# esp8266_db.net
KiCad netlist of a schematic drawn in EAGLE
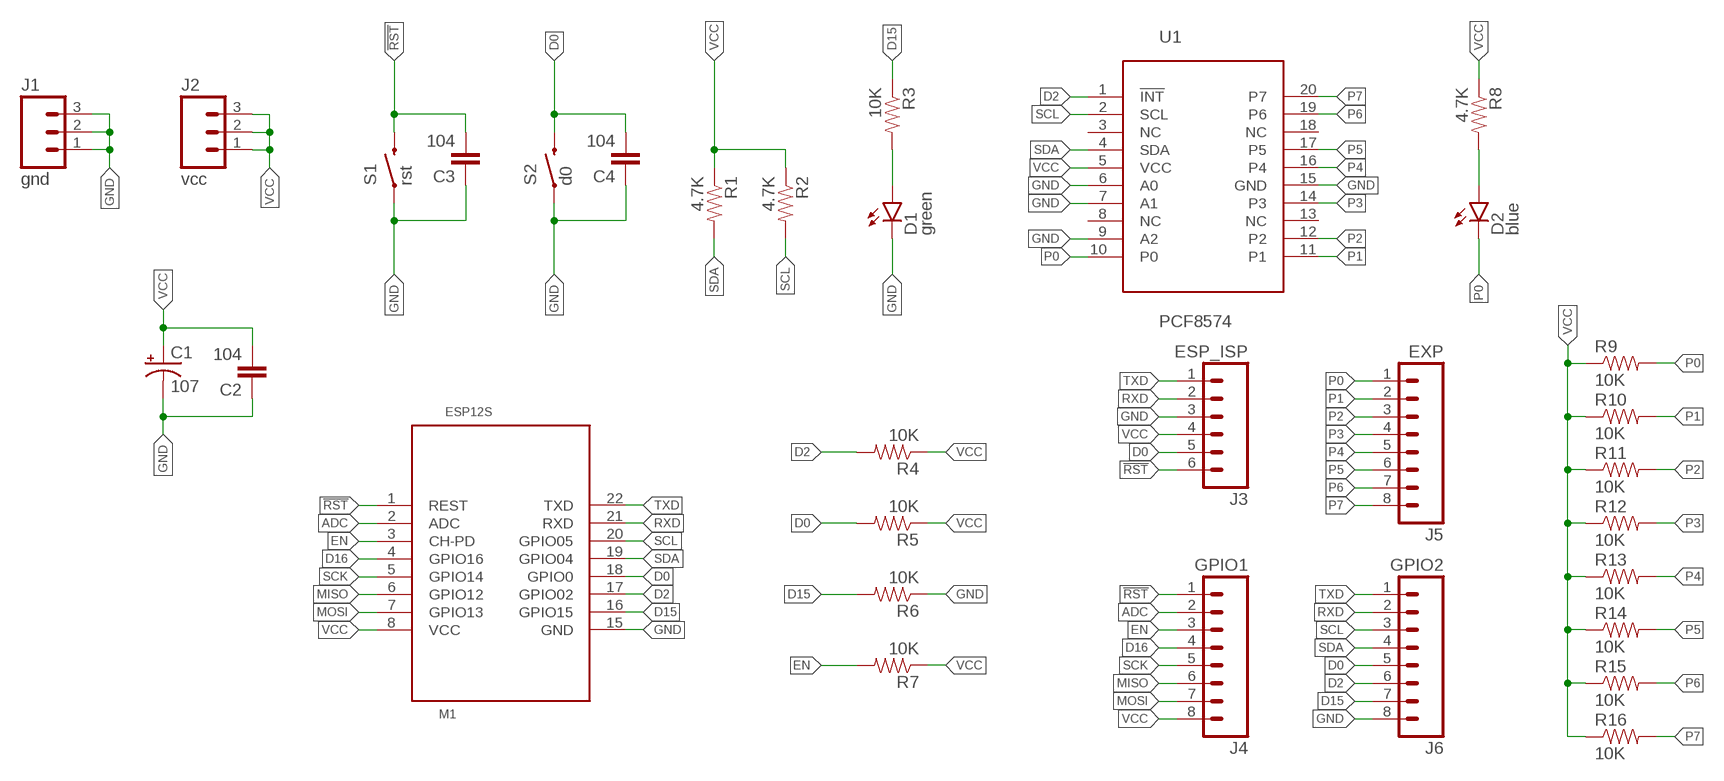
[diagram p0: schematic, sheet 1]

(export (version "E")
  (design (tool "Eeschema 10.0.6"))
  (components
    (comp (ref "C1")
      (value "107")
      (footprint "eagle-import:EIA3528")
      (libsource (lib "eagle-import") (part "CAP_POL3528"))
    )
    (comp (ref "C2")
      (value "104")
      (footprint "eagle-import:0603-CAP")
      (libsource (lib "eagle-import") (part "CAP0603-CAP"))
    )
    (comp (ref "C3")
      (value "104")
      (footprint "eagle-import:0603-CAP")
      (libsource (lib "eagle-import") (part "CAP0603-CAP"))
    )
    (comp (ref "C4")
      (value "104")
      (footprint "eagle-import:0603-CAP")
      (libsource (lib "eagle-import") (part "CAP0603-CAP"))
    )
    (comp (ref "D1")
      (value "green")
      (footprint "eagle-import:LED-0603-EASY")
      (libsource (lib "eagle-import") (part "LED-EASY"))
    )
    (comp (ref "D2")
      (value "blue")
      (footprint "eagle-import:LED-0603-EASY")
      (libsource (lib "eagle-import") (part "LED-EASY"))
    )
    (comp (ref "J1")
      (value "gnd")
      (footprint "eagle-import:1X03_NO_SILK")
      (libsource (lib "eagle-import") (part "M031X03_NO_SILK"))
    )
    (comp (ref "J2")
      (value "vcc")
      (footprint "eagle-import:1X03_NO_SILK")
      (libsource (lib "eagle-import") (part "M031X03_NO_SILK"))
    )
    (comp (ref "J3")
      (value "ESP_ISP")
      (footprint "eagle-import:1X06_NO_SILK")
      (libsource (lib "eagle-import") (part "M06NO_SILK_FEMALE_PTH"))
    )
    (comp (ref "J4")
      (value "GPIO1")
      (footprint "eagle-import:1X08_NO_SILK")
      (libsource (lib "eagle-import") (part "M08NO_SILK_FEMALE_PTH"))
    )
    (comp (ref "J5")
      (value "EXP")
      (footprint "eagle-import:1X08_NO_SILK")
      (libsource (lib "eagle-import") (part "M08NO_SILK_FEMALE_PTH"))
    )
    (comp (ref "J6")
      (value "GPIO2")
      (footprint "eagle-import:1X08_NO_SILK")
      (libsource (lib "eagle-import") (part "M08NO_SILK_FEMALE_PTH"))
    )
    (comp (ref "M1")
      (value "ESP12S")
      (footprint "eagle-import:LGA22-2.0-24X16MM-SIMPLE")
      (libsource (lib "eagle-import") (part "MODULE-WIFI-ESP8266-12E-SIMPLE"))
    )
    (comp (ref "R1")
      (value "4.7K")
      (footprint "eagle-import:0603-RES")
      (libsource (lib "eagle-import") (part "RESISTOR0603"))
    )
    (comp (ref "R2")
      (value "4.7K")
      (footprint "eagle-import:0603-RES")
      (libsource (lib "eagle-import") (part "RESISTOR0603"))
    )
    (comp (ref "R3")
      (value "10K")
      (footprint "eagle-import:0603-RES")
      (libsource (lib "eagle-import") (part "RESISTOR0603"))
    )
    (comp (ref "R4")
      (value "10K")
      (footprint "eagle-import:0603-RES")
      (libsource (lib "eagle-import") (part "RESISTOR0603"))
    )
    (comp (ref "R5")
      (value "10K")
      (footprint "eagle-import:0603-RES")
      (libsource (lib "eagle-import") (part "RESISTOR0603"))
    )
    (comp (ref "R6")
      (value "10K")
      (footprint "eagle-import:0603-RES")
      (libsource (lib "eagle-import") (part "RESISTOR0603"))
    )
    (comp (ref "R7")
      (value "10K")
      (footprint "eagle-import:0603-RES")
      (libsource (lib "eagle-import") (part "RESISTOR0603"))
    )
    (comp (ref "R8")
      (value "4.7K")
      (footprint "eagle-import:0603-RES")
      (libsource (lib "eagle-import") (part "RESISTOR0603"))
    )
    (comp (ref "R9")
      (value "10K")
      (footprint "eagle-import:0603-RES")
      (libsource (lib "eagle-import") (part "RESISTOR0603"))
    )
    (comp (ref "R10")
      (value "10K")
      (footprint "eagle-import:0603-RES")
      (libsource (lib "eagle-import") (part "RESISTOR0603"))
    )
    (comp (ref "R11")
      (value "10K")
      (footprint "eagle-import:0603-RES")
      (libsource (lib "eagle-import") (part "RESISTOR0603"))
    )
    (comp (ref "R12")
      (value "10K")
      (footprint "eagle-import:0603-RES")
      (libsource (lib "eagle-import") (part "RESISTOR0603"))
    )
    (comp (ref "R13")
      (value "10K")
      (footprint "eagle-import:0603-RES")
      (libsource (lib "eagle-import") (part "RESISTOR0603"))
    )
    (comp (ref "R14")
      (value "10K")
      (footprint "eagle-import:0603-RES")
      (libsource (lib "eagle-import") (part "RESISTOR0603"))
    )
    (comp (ref "R15")
      (value "10K")
      (footprint "eagle-import:0603-RES")
      (libsource (lib "eagle-import") (part "RESISTOR0603"))
    )
    (comp (ref "R16")
      (value "10K")
      (footprint "eagle-import:0603-RES")
      (libsource (lib "eagle-import") (part "RESISTOR0603"))
    )
    (comp (ref "S1")
      (value "rst")
      (footprint "eagle-import:TACTILE-PTH")
      (libsource (lib "eagle-import") (part "SWITCH-MOMENTARY-2PTH"))
    )
    (comp (ref "S2")
      (value "d0")
      (footprint "eagle-import:TACTILE-PTH")
      (libsource (lib "eagle-import") (part "SWITCH-MOMENTARY-2PTH"))
    )
    (comp (ref "U1")
      (value "PCF8574")
      (footprint "eagle-import:TSSOP20")
      (libsource (lib "eagle-import") (part "PCF8574"))
    )
  )
  (nets
    (net (code "1") (name "/~{RST}") (class "Default")
      (node (ref "C3") (pin "2") (pinfunction "2_2") (pintype "passive"))
      (node (ref "J3") (pin "6") (pinfunction "6_6") (pintype "passive"))
      (node (ref "J4") (pin "1") (pinfunction "1_1") (pintype "passive"))
      (node (ref "M1") (pin "1") (pinfunction "REST_1") (pintype "bidirectional"))
      (node (ref "S1") (pin "3") (pinfunction "2_3") (pintype "passive"))
    )
    (net (code "2") (name "ADC") (class "Default")
      (node (ref "J4") (pin "2") (pinfunction "2_2") (pintype "passive"))
      (node (ref "M1") (pin "2") (pinfunction "ADC_2") (pintype "bidirectional"))
    )
    (net (code "3") (name "D0") (class "Default")
      (node (ref "C4") (pin "2") (pinfunction "2_2") (pintype "passive"))
      (node (ref "J3") (pin "5") (pinfunction "5_5") (pintype "passive"))
      (node (ref "J6") (pin "5") (pinfunction "5_5") (pintype "passive"))
      (node (ref "M1") (pin "18") (pinfunction "GPIO0_18") (pintype "bidirectional"))
      (node (ref "R5") (pin "2") (pinfunction "2_2") (pintype "passive"))
      (node (ref "S2") (pin "3") (pinfunction "2_3") (pintype "passive"))
    )
    (net (code "4") (name "D2") (class "Default")
      (node (ref "J6") (pin "6") (pinfunction "6_6") (pintype "passive"))
      (node (ref "M1") (pin "17") (pinfunction "GPIO02_17") (pintype "bidirectional"))
      (node (ref "R4") (pin "2") (pinfunction "2_2") (pintype "passive"))
      (node (ref "U1") (pin "1") (pinfunction "~{INT}_1") (pintype "bidirectional"))
    )
    (net (code "5") (name "D15") (class "Default")
      (node (ref "J6") (pin "7") (pinfunction "7_7") (pintype "passive"))
      (node (ref "M1") (pin "16") (pinfunction "GPIO15_16") (pintype "bidirectional"))
      (node (ref "R3") (pin "1") (pinfunction "1_1") (pintype "passive"))
      (node (ref "R6") (pin "2") (pinfunction "2_2") (pintype "passive"))
    )
    (net (code "6") (name "D16") (class "Default")
      (node (ref "J4") (pin "4") (pinfunction "4_4") (pintype "passive"))
      (node (ref "M1") (pin "4") (pinfunction "GPIO16_4") (pintype "bidirectional"))
    )
    (net (code "7") (name "EN") (class "Default")
      (node (ref "J4") (pin "3") (pinfunction "3_3") (pintype "passive"))
      (node (ref "M1") (pin "3") (pinfunction "CH-PD_3") (pintype "bidirectional"))
      (node (ref "R7") (pin "2") (pinfunction "2_2") (pintype "passive"))
    )
    (net (code "8") (name "GND") (class "Default")
      (node (ref "C1") (pin "C") (pinfunction "-_C") (pintype "passive"))
      (node (ref "C2") (pin "1") (pinfunction "1_1") (pintype "passive"))
      (node (ref "C3") (pin "1") (pinfunction "1_1") (pintype "passive"))
      (node (ref "C4") (pin "1") (pinfunction "1_1") (pintype "passive"))
      (node (ref "D1") (pin "-") (pinfunction "C_-") (pintype "passive"))
      (node (ref "J1") (pin "1") (pinfunction "1_1") (pintype "passive"))
      (node (ref "J1") (pin "2") (pinfunction "2_2") (pintype "passive"))
      (node (ref "J1") (pin "3") (pinfunction "3_3") (pintype "passive"))
      (node (ref "J3") (pin "3") (pinfunction "3_3") (pintype "passive"))
      (node (ref "J6") (pin "8") (pinfunction "8_8") (pintype "passive"))
      (node (ref "M1") (pin "15") (pinfunction "GND_15") (pintype "bidirectional"))
      (node (ref "R6") (pin "1") (pinfunction "1_1") (pintype "passive"))
      (node (ref "S1") (pin "1") (pinfunction "1_1") (pintype "passive"))
      (node (ref "S2") (pin "1") (pinfunction "1_1") (pintype "passive"))
      (node (ref "U1") (pin "15") (pinfunction "GND_15") (pintype "bidirectional"))
      (node (ref "U1") (pin "6") (pinfunction "A0_6") (pintype "bidirectional"))
      (node (ref "U1") (pin "7") (pinfunction "A1_7") (pintype "bidirectional"))
      (node (ref "U1") (pin "9") (pinfunction "A2_9") (pintype "bidirectional"))
    )
    (net (code "9") (name "MISO") (class "Default")
      (node (ref "J4") (pin "6") (pinfunction "6_6") (pintype "passive"))
      (node (ref "M1") (pin "6") (pinfunction "GPIO12_6") (pintype "bidirectional"))
    )
    (net (code "10") (name "MOSI") (class "Default")
      (node (ref "J4") (pin "7") (pinfunction "7_7") (pintype "passive"))
      (node (ref "M1") (pin "7") (pinfunction "GPIO13_7") (pintype "bidirectional"))
    )
    (net (code "11") (name "Net-(D1-A)") (class "Default")
      (node (ref "D1") (pin "+") (pinfunction "A_+") (pintype "passive"))
      (node (ref "R3") (pin "2") (pinfunction "2_2") (pintype "passive"))
    )
    (net (code "12") (name "Net-(D2-A)") (class "Default")
      (node (ref "D2") (pin "+") (pinfunction "A_+") (pintype "passive"))
      (node (ref "R8") (pin "2") (pinfunction "2_2") (pintype "passive"))
    )
    (net (code "13") (name "P0") (class "Default")
      (node (ref "D2") (pin "-") (pinfunction "C_-") (pintype "passive"))
      (node (ref "J5") (pin "1") (pinfunction "1_1") (pintype "passive"))
      (node (ref "R9") (pin "2") (pinfunction "2_2") (pintype "passive"))
      (node (ref "U1") (pin "10") (pinfunction "P0_10") (pintype "bidirectional"))
    )
    (net (code "14") (name "P1") (class "Default")
      (node (ref "J5") (pin "2") (pinfunction "2_2") (pintype "passive"))
      (node (ref "R10") (pin "2") (pinfunction "2_2") (pintype "passive"))
      (node (ref "U1") (pin "11") (pinfunction "P1_11") (pintype "bidirectional"))
    )
    (net (code "15") (name "P2") (class "Default")
      (node (ref "J5") (pin "3") (pinfunction "3_3") (pintype "passive"))
      (node (ref "R11") (pin "2") (pinfunction "2_2") (pintype "passive"))
      (node (ref "U1") (pin "12") (pinfunction "P2_12") (pintype "bidirectional"))
    )
    (net (code "16") (name "P3") (class "Default")
      (node (ref "J5") (pin "4") (pinfunction "4_4") (pintype "passive"))
      (node (ref "R12") (pin "2") (pinfunction "2_2") (pintype "passive"))
      (node (ref "U1") (pin "14") (pinfunction "P3_14") (pintype "bidirectional"))
    )
    (net (code "17") (name "P4") (class "Default")
      (node (ref "J5") (pin "5") (pinfunction "5_5") (pintype "passive"))
      (node (ref "R13") (pin "2") (pinfunction "2_2") (pintype "passive"))
      (node (ref "U1") (pin "16") (pinfunction "P4_16") (pintype "bidirectional"))
    )
    (net (code "18") (name "P5") (class "Default")
      (node (ref "J5") (pin "6") (pinfunction "6_6") (pintype "passive"))
      (node (ref "R14") (pin "2") (pinfunction "2_2") (pintype "passive"))
      (node (ref "U1") (pin "17") (pinfunction "P5_17") (pintype "bidirectional"))
    )
    (net (code "19") (name "P6") (class "Default")
      (node (ref "J5") (pin "7") (pinfunction "7_7") (pintype "passive"))
      (node (ref "R15") (pin "2") (pinfunction "2_2") (pintype "passive"))
      (node (ref "U1") (pin "19") (pinfunction "P6_19") (pintype "bidirectional"))
    )
    (net (code "20") (name "P7") (class "Default")
      (node (ref "J5") (pin "8") (pinfunction "8_8") (pintype "passive"))
      (node (ref "R16") (pin "2") (pinfunction "2_2") (pintype "passive"))
      (node (ref "U1") (pin "20") (pinfunction "P7_20") (pintype "bidirectional"))
    )
    (net (code "21") (name "RXD") (class "Default")
      (node (ref "J3") (pin "2") (pinfunction "2_2") (pintype "passive"))
      (node (ref "J6") (pin "2") (pinfunction "2_2") (pintype "passive"))
      (node (ref "M1") (pin "21") (pinfunction "RXD_21") (pintype "bidirectional"))
    )
    (net (code "22") (name "SCK") (class "Default")
      (node (ref "J4") (pin "5") (pinfunction "5_5") (pintype "passive"))
      (node (ref "M1") (pin "5") (pinfunction "GPIO14_5") (pintype "bidirectional"))
    )
    (net (code "23") (name "SCL") (class "Default")
      (node (ref "J6") (pin "3") (pinfunction "3_3") (pintype "passive"))
      (node (ref "M1") (pin "20") (pinfunction "GPIO05_20") (pintype "bidirectional"))
      (node (ref "R2") (pin "2") (pinfunction "2_2") (pintype "passive"))
      (node (ref "U1") (pin "2") (pinfunction "SCL_2") (pintype "bidirectional"))
    )
    (net (code "24") (name "SDA") (class "Default")
      (node (ref "J6") (pin "4") (pinfunction "4_4") (pintype "passive"))
      (node (ref "M1") (pin "19") (pinfunction "GPIO04_19") (pintype "bidirectional"))
      (node (ref "R1") (pin "2") (pinfunction "2_2") (pintype "passive"))
      (node (ref "U1") (pin "4") (pinfunction "SDA_4") (pintype "bidirectional"))
    )
    (net (code "25") (name "TXD") (class "Default")
      (node (ref "J3") (pin "1") (pinfunction "1_1") (pintype "passive"))
      (node (ref "J6") (pin "1") (pinfunction "1_1") (pintype "passive"))
      (node (ref "M1") (pin "22") (pinfunction "TXD_22") (pintype "bidirectional"))
    )
    (net (code "26") (name "VCC") (class "Default")
      (node (ref "C1") (pin "A") (pinfunction "+_A") (pintype "passive"))
      (node (ref "C2") (pin "2") (pinfunction "2_2") (pintype "passive"))
      (node (ref "J2") (pin "1") (pinfunction "1_1") (pintype "passive"))
      (node (ref "J2") (pin "2") (pinfunction "2_2") (pintype "passive"))
      (node (ref "J2") (pin "3") (pinfunction "3_3") (pintype "passive"))
      (node (ref "J3") (pin "4") (pinfunction "4_4") (pintype "passive"))
      (node (ref "J4") (pin "8") (pinfunction "8_8") (pintype "passive"))
      (node (ref "M1") (pin "8") (pinfunction "VCC_8") (pintype "bidirectional"))
      (node (ref "R1") (pin "1") (pinfunction "1_1") (pintype "passive"))
      (node (ref "R10") (pin "1") (pinfunction "1_1") (pintype "passive"))
      (node (ref "R11") (pin "1") (pinfunction "1_1") (pintype "passive"))
      (node (ref "R12") (pin "1") (pinfunction "1_1") (pintype "passive"))
      (node (ref "R13") (pin "1") (pinfunction "1_1") (pintype "passive"))
      (node (ref "R14") (pin "1") (pinfunction "1_1") (pintype "passive"))
      (node (ref "R15") (pin "1") (pinfunction "1_1") (pintype "passive"))
      (node (ref "R16") (pin "1") (pinfunction "1_1") (pintype "passive"))
      (node (ref "R2") (pin "1") (pinfunction "1_1") (pintype "passive"))
      (node (ref "R4") (pin "1") (pinfunction "1_1") (pintype "passive"))
      (node (ref "R5") (pin "1") (pinfunction "1_1") (pintype "passive"))
      (node (ref "R7") (pin "1") (pinfunction "1_1") (pintype "passive"))
      (node (ref "R8") (pin "1") (pinfunction "1_1") (pintype "passive"))
      (node (ref "R9") (pin "1") (pinfunction "1_1") (pintype "passive"))
      (node (ref "U1") (pin "5") (pinfunction "VCC_5") (pintype "bidirectional"))
    )
    (net (code "27") (name "unconnected-(U1-NC-Pad3)") (class "Default")
      (node (ref "U1") (pin "3") (pinfunction "NC_3") (pintype "bidirectional"))
    )
    (net (code "28") (name "unconnected-(U1-NC-Pad8)") (class "Default")
      (node (ref "U1") (pin "8") (pinfunction "NC_8") (pintype "bidirectional"))
    )
    (net (code "29") (name "unconnected-(U1-NC-Pad13)") (class "Default")
      (node (ref "U1") (pin "13") (pinfunction "NC_13") (pintype "bidirectional"))
    )
    (net (code "30") (name "unconnected-(U1-NC-Pad18)") (class "Default")
      (node (ref "U1") (pin "18") (pinfunction "NC_18") (pintype "bidirectional"))
    )
  )
)
